# Communications.net
KiCad netlist of a schematic drawn in Altium Designer
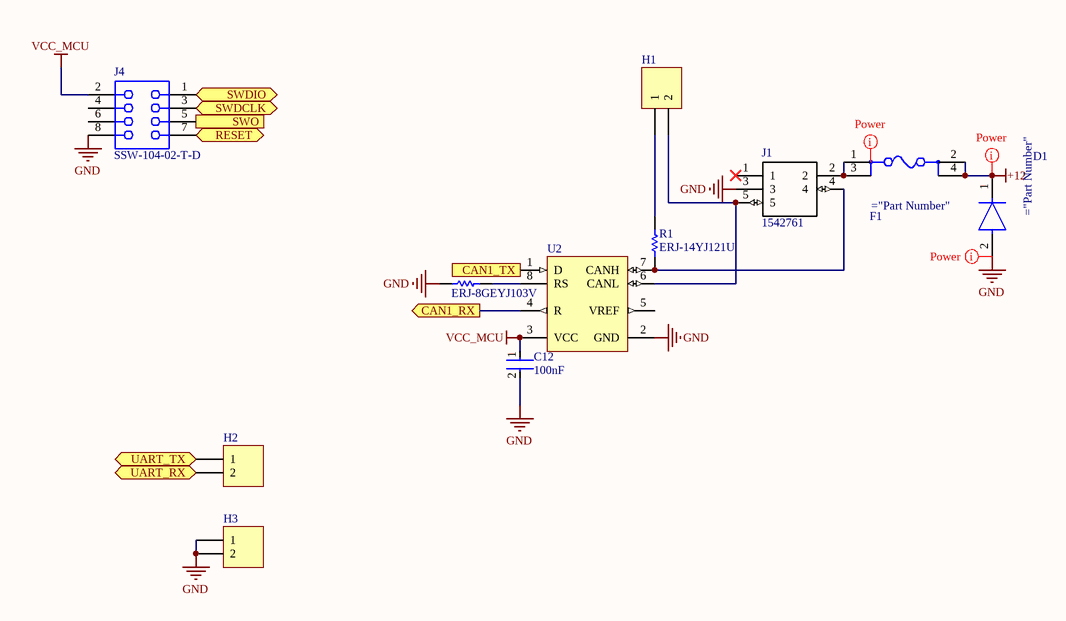
[diagram p0: Communications.SchDoc]

(export (version "E")
  (design (tool "Eeschema 10.0.6"))
  (components
    (comp (ref "C12")
      (value "100nF")
      (footprint "Kemet_C0603_IPC_A")
      (description "CAP CER 0.1UF 100NF 50V X7R 0603 C0603C104K5RACTU")
      (libsource (lib "UNK_Kemet_C0603C104K5RACTU_eec") (part "C0603C104K5RACTU"))
    )
    (comp (ref "D1")
      (value "S1J-13-F")
      (footprint "Diodes_SMA_0")
      (libsource (lib "Diode_Diodes_S1J-13-F_eec") (part "S1J-13-F"))
    )
    (comp (ref "F1")
      (value "3557-2")
      (footprint "Keystone_3557-2_0")
      (libsource (lib "Fuse_Keystone_3557-2_eec") (part "3557-2"))
    )
    (comp (ref "H1")
      (value "Header 0")
      (footprint "HDR1X2")
      (description "Header, 2-Pin")
      (fields (field (name "PUBLISHER") "Altium Limited"))
      (libsource (lib "") (part "Header 2_1"))
    )
    (comp (ref "H2")
      (value "Header 0")
      (footprint "HDR1X2")
      (description "Header, 2-Pin")
      (fields (field (name "PUBLISHER") "Altium Limited"))
      (libsource (lib "Miscellaneous Connectors") (part "Header 2"))
    )
    (comp (ref "H3")
      (value "Header 0")
      (footprint "HDR1X2")
      (description "Header, 2-Pin")
      (fields (field (name "PUBLISHER") "Altium Limited"))
      (libsource (lib "Miscellaneous Connectors") (part "Header 2"))
    )
    (comp (ref "J1")
      (value "1542761")
      (footprint "SamacSys:1542761")
      (description "Connector")
      (fields (field (name "MOUSER PART NUMBER") "651-1542761") (field (name "RS PART NUMBER") "8025583"))
      (libsource (lib "*") (part "1542761"))
    )
    (comp (ref "J4")
      (value "SSW-104-02-T-D")
      (footprint "SMTC-SSW-104-02-X-D")
      (description "SQ Post Socket, Through-hole, Vertical, -55 to 105 degC, 2.54mm Pitch, 8-Pin, Female, RoHS")
      (fields (field (name "MANUFACTURER") "Samtec"))
      (libsource (lib "Altium Content Vault") (part "SMTC-SSW-104-X-X-D"))
    )
    (comp (ref "R1")
      (value "ERJ-14YJ121U")
      (footprint "RESC3225X70X50ML20T20")
      (description "120Ohm")
      (fields (field (name "MANUFACTURER") "Panasonic"))
      (libsource (lib "Altium Content Vault") (part "RES"))
    )
    (comp (ref "R9")
      (value "ERJ-8GEYJ103V")
      (footprint "RESC3216X70X50NL05T20")
      (description "10k")
      (fields (field (name "MANUFACTURER") "Panasonic"))
      (libsource (lib "Altium Content Vault") (part "RES"))
    )
    (comp (ref "U2")
      (value "SN65HVD230D")
      (footprint "D0008A_M")
      (description "CAN Bus Transceiver, 3.3 V, -40 to 85 degC, 8-Pin SOIC (D), Green (RoHS & no Sb/Br), Tube")
      (fields (field (name "GENERIC PART NUMBER") "SN65HVD230"))
      (libsource (lib "Altium Content Vault") (part "TI-SN65HVD230D-SOIC_D-8"))
    )
  )
  (nets
    (net (code "1") (name "+12") (class "Default")
      (node (ref "D1") (pin "1") (pinfunction "C_1") (pintype "passive"))
      (node (ref "F1") (pin "2") (pinfunction "2_2") (pintype "passive"))
      (node (ref "F1") (pin "4") (pinfunction "4_4") (pintype "passive"))
    )
    (net (code "2") (name "/CAN1_RX") (class "Default")
      (node (ref "U2") (pin "4") (pinfunction "R_4") (pintype "output"))
    )
    (net (code "3") (name "/CAN1_TX") (class "Default")
      (node (ref "U2") (pin "1") (pinfunction "D_1") (pintype "input"))
    )
    (net (code "4") (name "/RESET") (class "Default")
      (node (ref "J4") (pin "7") (pinfunction "7_7") (pintype "passive"))
    )
    (net (code "5") (name "/SWDCLK") (class "Default")
      (node (ref "J4") (pin "3") (pinfunction "3_3") (pintype "passive"))
    )
    (net (code "6") (name "/SWDIO") (class "Default")
      (node (ref "J4") (pin "1") (pinfunction "1_1") (pintype "passive"))
    )
    (net (code "7") (name "/SWO") (class "Default")
      (node (ref "J4") (pin "5") (pinfunction "5_5") (pintype "passive"))
    )
    (net (code "8") (name "/UART_RX") (class "Default")
      (node (ref "H2") (pin "2") (pinfunction "2_2") (pintype "passive"))
    )
    (net (code "9") (name "/UART_TX") (class "Default")
      (node (ref "H2") (pin "1") (pinfunction "1_1") (pintype "passive"))
    )
    (net (code "10") (name "GND") (class "Default")
      (node (ref "C12") (pin "2") (pinfunction "2_2") (pintype "passive"))
      (node (ref "D1") (pin "2") (pinfunction "A_2") (pintype "passive"))
      (node (ref "H3") (pin "1") (pinfunction "1_1") (pintype "passive"))
      (node (ref "H3") (pin "2") (pinfunction "2_2") (pintype "passive"))
      (node (ref "J1") (pin "3") (pinfunction "3_3") (pintype "power_in"))
      (node (ref "J4") (pin "8") (pinfunction "8_8") (pintype "passive"))
      (node (ref "R9") (pin "2") (pinfunction "2_2") (pintype "passive"))
      (node (ref "U2") (pin "2") (pinfunction "GND_2") (pintype "power_in"))
    )
    (net (code "11") (name "Net-(F1-Pad1)") (class "Default")
      (node (ref "F1") (pin "1") (pinfunction "1_1") (pintype "passive"))
      (node (ref "F1") (pin "3") (pinfunction "3_3") (pintype "passive"))
      (node (ref "J1") (pin "2") (pinfunction "2_2") (pintype "power_in"))
    )
    (net (code "12") (name "Net-(H1-Pad1)") (class "Default")
      (node (ref "H1") (pin "1") (pinfunction "1_1") (pintype "passive"))
      (node (ref "R1") (pin "2") (pinfunction "2_2") (pintype "passive"))
    )
    (net (code "13") (name "Net-(U2-CANH)") (class "Default")
      (node (ref "J1") (pin "4") (pinfunction "4_4") (pintype "bidirectional"))
      (node (ref "R1") (pin "1") (pinfunction "1_1") (pintype "passive"))
      (node (ref "U2") (pin "7") (pinfunction "CANH_7") (pintype "bidirectional"))
    )
    (net (code "14") (name "Net-(U2-CANL)") (class "Default")
      (node (ref "H1") (pin "2") (pinfunction "2_2") (pintype "passive"))
      (node (ref "J1") (pin "5") (pinfunction "5_5") (pintype "bidirectional"))
      (node (ref "U2") (pin "6") (pinfunction "CANL_6") (pintype "bidirectional"))
    )
    (net (code "15") (name "Net-(U2-RS)") (class "Default")
      (node (ref "R9") (pin "1") (pinfunction "1_1") (pintype "passive"))
      (node (ref "U2") (pin "8") (pinfunction "RS_8") (pintype "passive"))
    )
    (net (code "16") (name "VCC_MCU") (class "Default")
      (node (ref "C12") (pin "1") (pinfunction "1_1") (pintype "passive"))
      (node (ref "J4") (pin "2") (pinfunction "2_2") (pintype "passive"))
      (node (ref "U2") (pin "3") (pinfunction "VCC_3") (pintype "power_in"))
    )
    (net (code "17") (name "unconnected-(J1-Pad1)") (class "Default")
      (node (ref "J1") (pin "1") (pinfunction "1_1") (pintype "passive+no_connect"))
    )
    (net (code "18") (name "unconnected-(J4-Pad4)") (class "Default")
      (node (ref "J4") (pin "4") (pinfunction "4_4") (pintype "passive"))
    )
    (net (code "19") (name "unconnected-(J4-Pad6)") (class "Default")
      (node (ref "J4") (pin "6") (pinfunction "6_6") (pintype "passive"))
    )
    (net (code "20") (name "unconnected-(U2-VREF-Pad5)") (class "Default")
      (node (ref "U2") (pin "5") (pinfunction "VREF_5") (pintype "output"))
    )
  )
)
